# Sensores_DELANTE_Y_ATRAS.net
KiCad netlist of a schematic drawn in EAGLE
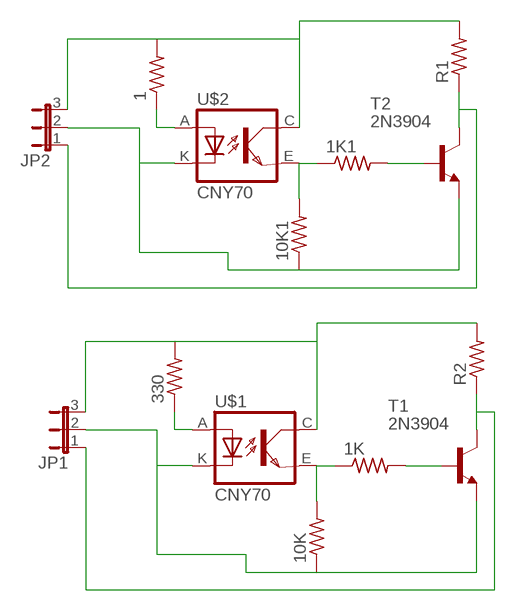
[diagram p0: schematic, sheet 1]

(export (version "E")
  (design (tool "Eeschema 10.0.6"))
  (components
    (comp (ref "1")
      (value "R-US_0309/10")
      (footprint "eagle-import:0309_10")
      (libsource (lib "eagle-import") (part "R-US_0309/10"))
    )
    (comp (ref "1K")
      (value "R-US_0309/10")
      (footprint "eagle-import:0309_10")
      (libsource (lib "eagle-import") (part "R-US_0309/10"))
    )
    (comp (ref "1K1")
      (value "R-US_0309/10")
      (footprint "eagle-import:0309_10")
      (libsource (lib "eagle-import") (part "R-US_0309/10"))
    )
    (comp (ref "10K")
      (value "R-US_0309/10")
      (footprint "eagle-import:0309_10")
      (libsource (lib "eagle-import") (part "R-US_0309/10"))
    )
    (comp (ref "10K1")
      (value "R-US_0309/10")
      (footprint "eagle-import:0309_10")
      (libsource (lib "eagle-import") (part "R-US_0309/10"))
    )
    (comp (ref "330")
      (value "R-US_0309/10")
      (footprint "eagle-import:0309_10")
      (libsource (lib "eagle-import") (part "R-US_0309/10"))
    )
    (comp (ref "JP1")
      (value "JP2E")
      (footprint "eagle-import:JP2")
      (libsource (lib "eagle-import") (part "JP2E"))
    )
    (comp (ref "JP2")
      (value "JP2E")
      (footprint "eagle-import:JP2")
      (libsource (lib "eagle-import") (part "JP2E"))
    )
    (comp (ref "R1")
      (value "R-US_0309/10")
      (footprint "eagle-import:0309_10")
      (libsource (lib "eagle-import") (part "R-US_0309/10"))
    )
    (comp (ref "R2")
      (value "R-US_0309/10")
      (footprint "eagle-import:0309_10")
      (libsource (lib "eagle-import") (part "R-US_0309/10"))
    )
    (comp (ref "T1")
      (value "2N3904")
      (footprint "eagle-import:TO92")
      (libsource (lib "eagle-import") (part "2N3904"))
    )
    (comp (ref "T2")
      (value "2N3904")
      (footprint "eagle-import:TO92")
      (libsource (lib "eagle-import") (part "2N3904"))
    )
    (comp (ref "U$1")
      (value "CNY70")
      (footprint "eagle-import:4")
      (libsource (lib "eagle-import") (part "CNY70"))
    )
    (comp (ref "U$2")
      (value "CNY70")
      (footprint "eagle-import:4")
      (libsource (lib "eagle-import") (part "CNY70"))
    )
  )
  (nets
    (net (code "1") (name "Net-(1-Pad1)") (class "Default")
      (node (ref "1") (pin "1") (pinfunction "1_1") (pintype "passive"))
      (node (ref "U$2") (pin "A") (pinfunction "A_A") (pintype "passive"))
    )
    (net (code "2") (name "Net-(330-Pad1)") (class "Default")
      (node (ref "330") (pin "1") (pinfunction "1_1") (pintype "passive"))
      (node (ref "U$1") (pin "A") (pinfunction "A_A") (pintype "passive"))
    )
    (net (code "3") (name "Net-(T1-B)") (class "Default")
      (node (ref "1K") (pin "2") (pinfunction "2_2") (pintype "passive"))
      (node (ref "T1") (pin "2") (pinfunction "B_2") (pintype "passive"))
    )
    (net (code "4") (name "Net-(T1-C)") (class "Default")
      (node (ref "JP1") (pin "1") (pinfunction "1_1") (pintype "passive"))
      (node (ref "R2") (pin "1") (pinfunction "1_1") (pintype "passive"))
      (node (ref "T1") (pin "1") (pinfunction "C_1") (pintype "passive"))
    )
    (net (code "5") (name "Net-(T1-E)") (class "Default")
      (node (ref "10K") (pin "1") (pinfunction "1_1") (pintype "passive"))
      (node (ref "JP1") (pin "2") (pinfunction "2_2") (pintype "passive"))
      (node (ref "T1") (pin "3") (pinfunction "E_3") (pintype "passive"))
      (node (ref "U$1") (pin "K") (pinfunction "C_K") (pintype "passive"))
    )
    (net (code "6") (name "Net-(T2-B)") (class "Default")
      (node (ref "1K1") (pin "2") (pinfunction "2_2") (pintype "passive"))
      (node (ref "T2") (pin "2") (pinfunction "B_2") (pintype "passive"))
    )
    (net (code "7") (name "Net-(T2-C)") (class "Default")
      (node (ref "JP2") (pin "1") (pinfunction "1_1") (pintype "passive"))
      (node (ref "R1") (pin "1") (pinfunction "1_1") (pintype "passive"))
      (node (ref "T2") (pin "1") (pinfunction "C_1") (pintype "passive"))
    )
    (net (code "8") (name "Net-(T2-E)") (class "Default")
      (node (ref "10K1") (pin "1") (pinfunction "1_1") (pintype "passive"))
      (node (ref "JP2") (pin "2") (pinfunction "2_2") (pintype "passive"))
      (node (ref "T2") (pin "3") (pinfunction "E_3") (pintype "passive"))
      (node (ref "U$2") (pin "K") (pinfunction "C_K") (pintype "passive"))
    )
    (net (code "9") (name "Net-(U$1-COL)") (class "Default")
      (node (ref "330") (pin "2") (pinfunction "2_2") (pintype "passive"))
      (node (ref "JP1") (pin "3") (pinfunction "3_3") (pintype "passive"))
      (node (ref "R2") (pin "2") (pinfunction "2_2") (pintype "passive"))
      (node (ref "U$1") (pin "C") (pinfunction "COL_C") (pintype "passive"))
    )
    (net (code "10") (name "Net-(U$1-EMI)") (class "Default")
      (node (ref "10K") (pin "2") (pinfunction "2_2") (pintype "passive"))
      (node (ref "1K") (pin "1") (pinfunction "1_1") (pintype "passive"))
      (node (ref "U$1") (pin "E") (pinfunction "EMI_E") (pintype "passive"))
    )
    (net (code "11") (name "Net-(U$2-COL)") (class "Default")
      (node (ref "1") (pin "2") (pinfunction "2_2") (pintype "passive"))
      (node (ref "JP2") (pin "3") (pinfunction "3_3") (pintype "passive"))
      (node (ref "R1") (pin "2") (pinfunction "2_2") (pintype "passive"))
      (node (ref "U$2") (pin "C") (pinfunction "COL_C") (pintype "passive"))
    )
    (net (code "12") (name "Net-(U$2-EMI)") (class "Default")
      (node (ref "10K1") (pin "2") (pinfunction "2_2") (pintype "passive"))
      (node (ref "1K1") (pin "1") (pinfunction "1_1") (pintype "passive"))
      (node (ref "U$2") (pin "E") (pinfunction "EMI_E") (pintype "passive"))
    )
  )
)
